# design.net
KiCad netlist of a schematic drawn in Altium Designer
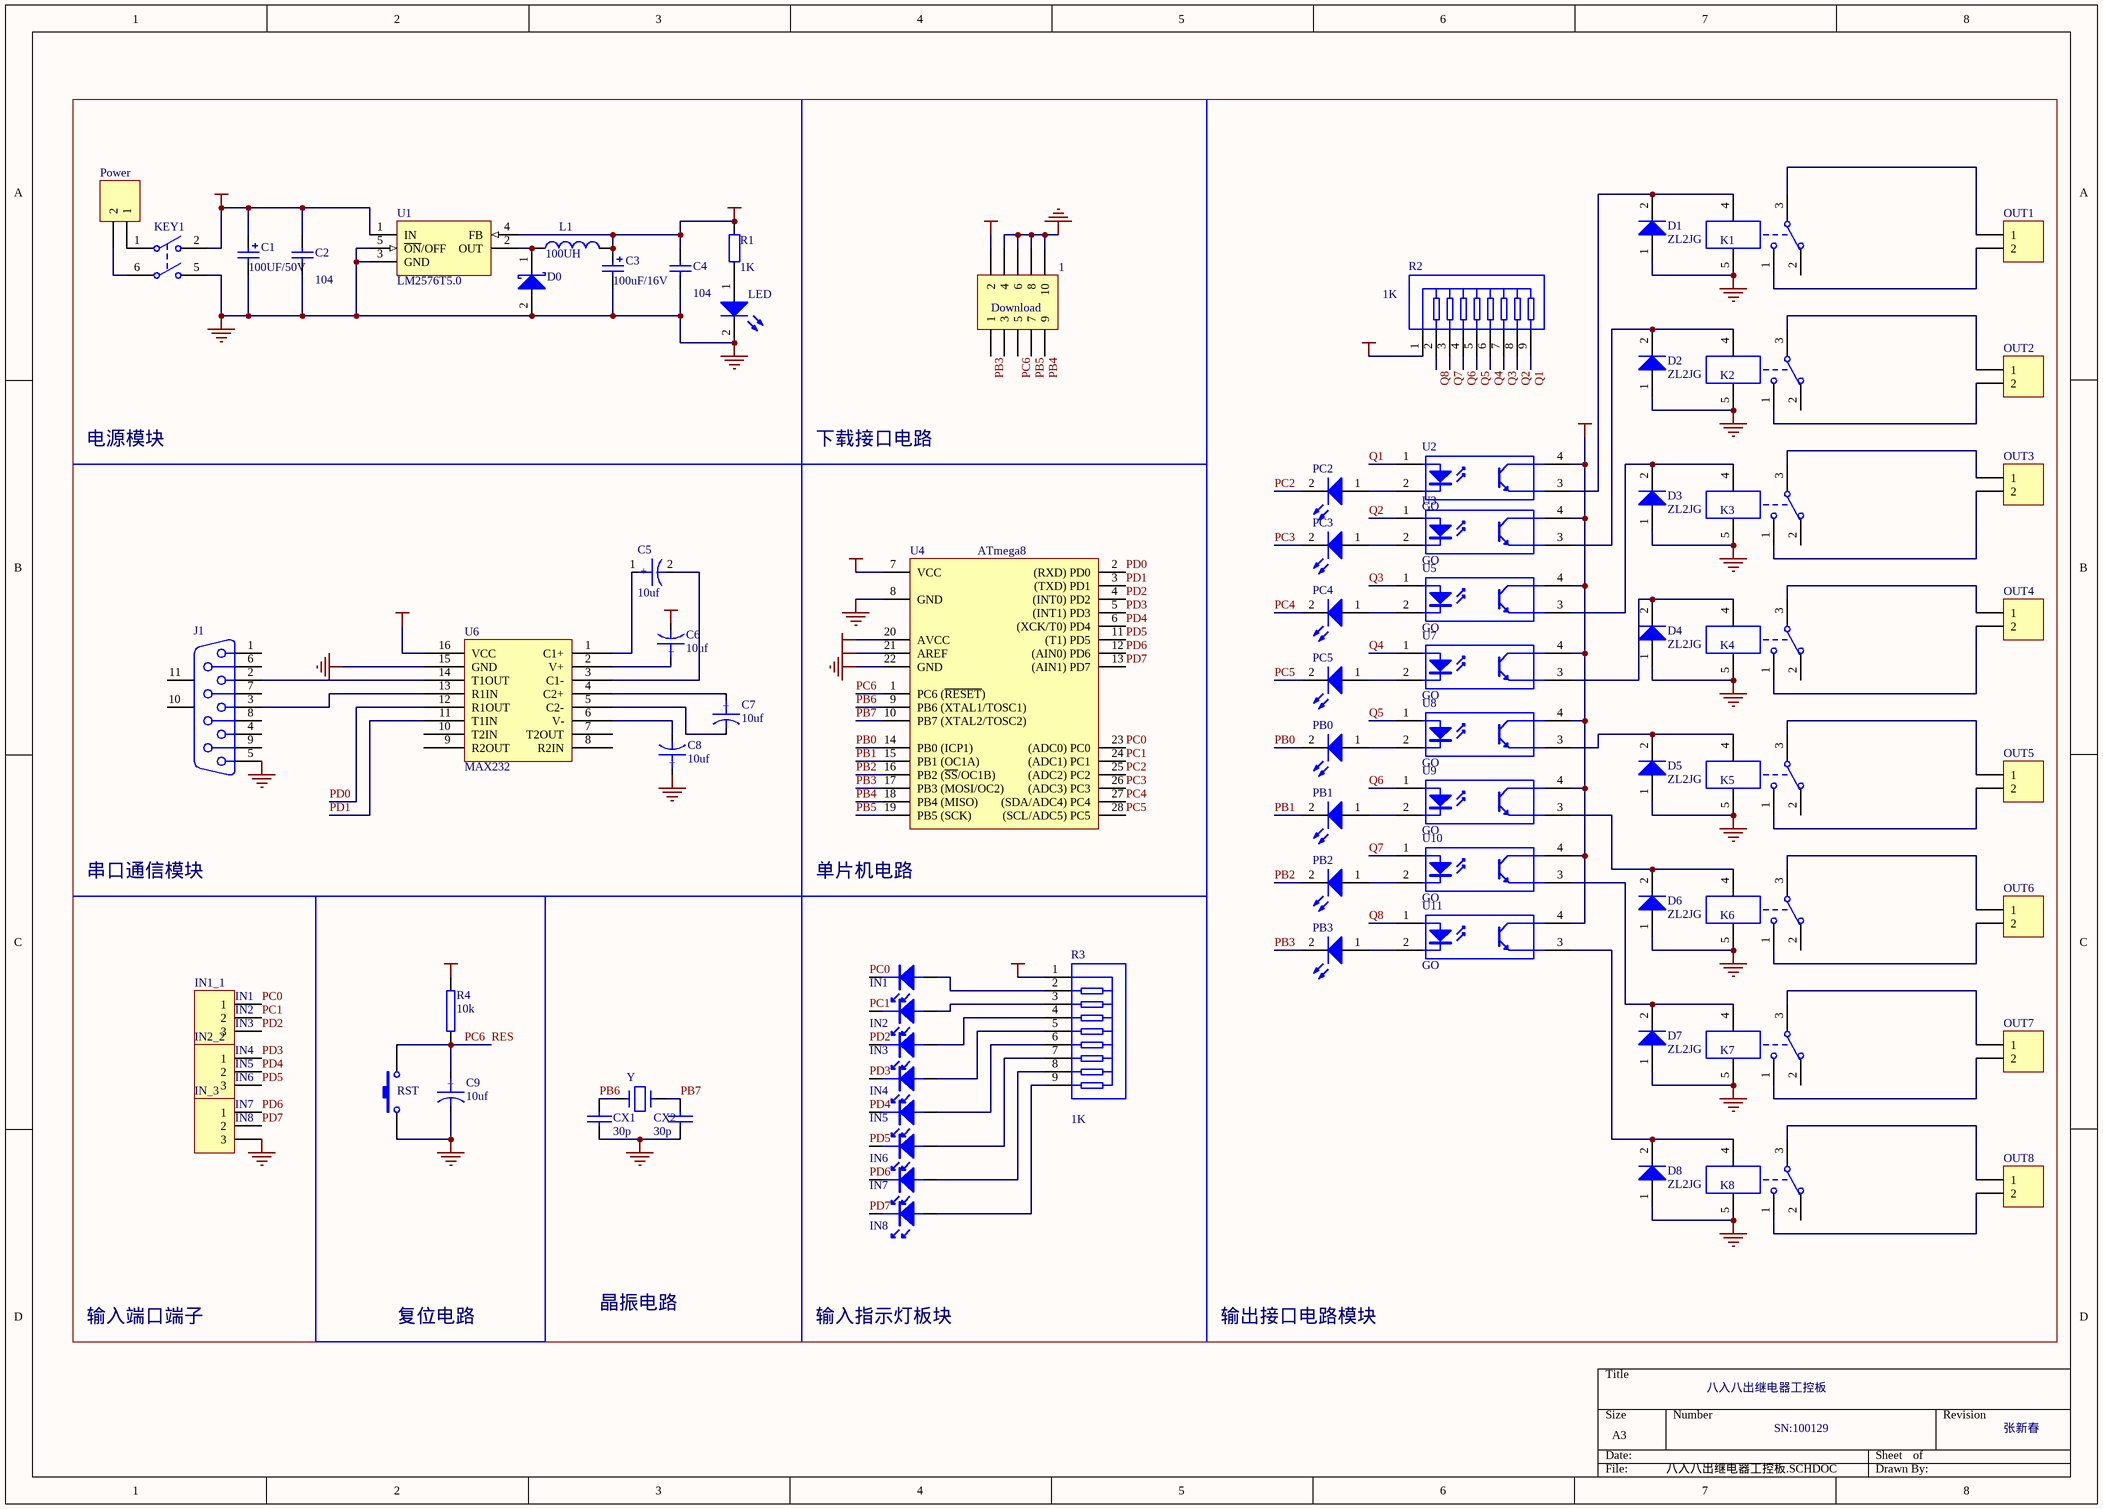
[diagram p0: 八入八出继电器工控板.SCHDOC]

(export (version "E")
  (design (tool "Eeschema 10.0.6"))
  (components
    (comp (ref "1")
      (value "Download")
      (footprint "HDR-2x5")
      (description "Header, 5-Pin, Dual row")
      (fields (field (name "PUBLISHER") "Altium Limited"))
      (libsource (lib "Miscellaneous Connectors") (part "Header 5X2"))
    )
    (comp (ref "C1")
      (value "100UF/50V")
      (footprint "C-DJ-6")
      (description "电解电容")
      (fields (field (name "Comment") "DJDR") (field (name "PUBLISHER") "Altium Limited"))
      (libsource (lib "zxcourhc") (part "DJDR"))
    )
    (comp (ref "C2")
      (value "104")
      (footprint "CPDR")
      (description "瓷片电容")
      (fields (field (name "Comment") "CPDR") (field (name "PUBLISHER") "Altium Limited"))
      (libsource (lib "zxcourhc") (part "CPDR"))
    )
    (comp (ref "C3")
      (value "100uF/16V")
      (footprint "C-DJ-6")
      (description "电解电容")
      (fields (field (name "Comment") "DJDR") (field (name "PUBLISHER") "Altium Limited"))
      (libsource (lib "zxcourhc") (part "DJDR"))
    )
    (comp (ref "C4")
      (value "104")
      (footprint "CPDR")
      (description "瓷片电容")
      (fields (field (name "Comment") "CPDR") (field (name "PUBLISHER") "Altium Limited"))
      (libsource (lib "zxcourhc") (part "CPDR"))
    )
    (comp (ref "C5")
      (value "10uf")
      (footprint "C-DJ-4")
      (description "Capacitor")
      (libsource (lib "") (part "CAPACITOR POL_1"))
    )
    (comp (ref "C6")
      (value "10uf")
      (footprint "C-DJ-4")
      (description "Capacitor")
      (libsource (lib "*") (part "CAPACITOR POL"))
    )
    (comp (ref "C7")
      (value "10uf")
      (footprint "C-DJ-4")
      (description "Capacitor")
      (libsource (lib "*") (part "CAPACITOR POL"))
    )
    (comp (ref "C8")
      (value "10uf")
      (footprint "C-DJ-4")
      (description "Capacitor")
      (libsource (lib "*") (part "CAPACITOR POL"))
    )
    (comp (ref "C9")
      (value "10uf")
      (footprint "C-DJ-4")
      (description "Capacitor")
      (libsource (lib "*") (part "CAPACITOR POL"))
    )
    (comp (ref "CX1")
      (value "30p")
      (footprint "HDR1X2")
      (description "Capacitor")
      (libsource (lib "*") (part "CAP"))
    )
    (comp (ref "CX2")
      (value "30p")
      (footprint "HDR1X2")
      (description "Capacitor")
      (libsource (lib "*") (part "CAP"))
    )
    (comp (ref "D0")
      (value "WY2JG")
      (footprint "ZCDZL")
      (description "稳压二级管")
      (fields (field (name "PUBLISHER") "Altium Limited"))
      (libsource (lib "zxcourhc") (part "WY2JG"))
    )
    (comp (ref "D1")
      (value "ZL2JG")
      (footprint "D-ZL-10")
      (description "整流二极管")
      (fields (field (name "PUBLISHER") "Altium Limited"))
      (libsource (lib "zxcourhc") (part "ZL2JG"))
    )
    (comp (ref "D2")
      (value "ZL2JG")
      (footprint "D-ZL-10")
      (description "整流二极管")
      (fields (field (name "PUBLISHER") "Altium Limited"))
      (libsource (lib "zxcourhc") (part "ZL2JG"))
    )
    (comp (ref "D3")
      (value "ZL2JG")
      (footprint "D-ZL-10")
      (description "整流二极管")
      (fields (field (name "PUBLISHER") "Altium Limited"))
      (libsource (lib "zxcourhc") (part "ZL2JG"))
    )
    (comp (ref "D4")
      (value "ZL2JG")
      (footprint "D-ZL-10")
      (description "整流二极管")
      (fields (field (name "PUBLISHER") "Altium Limited"))
      (libsource (lib "zxcourhc") (part "ZL2JG"))
    )
    (comp (ref "D5")
      (value "ZL2JG")
      (footprint "D-ZL-10")
      (description "整流二极管")
      (fields (field (name "PUBLISHER") "Altium Limited"))
      (libsource (lib "zxcourhc") (part "ZL2JG"))
    )
    (comp (ref "D6")
      (value "ZL2JG")
      (footprint "D-ZL-10")
      (description "整流二极管")
      (fields (field (name "PUBLISHER") "Altium Limited"))
      (libsource (lib "zxcourhc") (part "ZL2JG"))
    )
    (comp (ref "D7")
      (value "ZL2JG")
      (footprint "D-ZL-10")
      (description "整流二极管")
      (fields (field (name "PUBLISHER") "Altium Limited"))
      (libsource (lib "zxcourhc") (part "ZL2JG"))
    )
    (comp (ref "D8")
      (value "ZL2JG")
      (footprint "D-ZL-10")
      (description "整流二极管")
      (fields (field (name "PUBLISHER") "Altium Limited"))
      (libsource (lib "zxcourhc") (part "ZL2JG"))
    )
    (comp (ref "IN1") (value "LED") (footprint "HDR1X2") (libsource (lib "OldCow1 (1)") (part "LED")))
    (comp (ref "IN1_1")
      (value "PZ_3")
      (footprint "JK128_3")
      (description "排针——3")
      (fields (field (name "PUBLISHER") "Altium Limited"))
      (libsource (lib "zxcourhc") (part "PZ_3"))
    )
    (comp (ref "IN2") (value "LED") (footprint "HDR1X2") (libsource (lib "OldCow1 (1)") (part "LED")))
    (comp (ref "IN2_2")
      (value "PZ_3")
      (footprint "JK128_3")
      (description "排针——3")
      (fields (field (name "PUBLISHER") "Altium Limited"))
      (libsource (lib "zxcourhc") (part "PZ_3"))
    )
    (comp (ref "IN3") (value "LED") (footprint "HDR1X2") (libsource (lib "OldCow1 (1)") (part "LED")))
    (comp (ref "IN4") (value "LED") (footprint "HDR1X2") (libsource (lib "OldCow1 (1)") (part "LED")))
    (comp (ref "IN5") (value "LED") (footprint "HDR1X2") (libsource (lib "OldCow1 (1)") (part "LED")))
    (comp (ref "IN6") (value "LED") (footprint "HDR1X2") (libsource (lib "OldCow1 (1)") (part "LED")))
    (comp (ref "IN7") (value "LED") (footprint "HDR1X2") (libsource (lib "OldCow1 (1)") (part "LED")))
    (comp (ref "IN8") (value "LED") (footprint "HDR1X2") (libsource (lib "OldCow1 (1)") (part "LED")))
    (comp (ref "IN_3")
      (value "~")
      (footprint "JK128_3")
      (description "排针——3")
      (fields (field (name "PUBLISHER") "Altium Limited"))
      (libsource (lib "zxcourhc") (part "PZ_3"))
    )
    (comp (ref "J1")
      (value "D Connector 9")
      (footprint "DSUB1.385-2H9")
      (description "Receptacle Assembly, 9 Position, Right Angle")
      (fields (field (name "PUBLISHER") "Altium Limited"))
      (libsource (lib "Miscellaneous Connectors") (part "D Connector 9"))
    )
    (comp (ref "K1")
      (value "JDQYCK")
      (footprint "JQC-3F/T73")
      (description "继电器——1常开1常闭")
      (fields (field (name "PUBLISHER") "Altium Limited"))
      (libsource (lib "zxcourhc") (part "JDQYCK"))
    )
    (comp (ref "K2")
      (value "JDQYCK")
      (footprint "JQC-3F/T73")
      (description "继电器——1常开1常闭")
      (fields (field (name "PUBLISHER") "Altium Limited"))
      (libsource (lib "zxcourhc") (part "JDQYCK"))
    )
    (comp (ref "K3")
      (value "JDQYCK")
      (footprint "JQC-3F/T73")
      (description "继电器——1常开1常闭")
      (fields (field (name "PUBLISHER") "Altium Limited"))
      (libsource (lib "zxcourhc") (part "JDQYCK"))
    )
    (comp (ref "K4")
      (value "JDQYCK")
      (footprint "JQC-3F/T73")
      (description "继电器——1常开1常闭")
      (fields (field (name "PUBLISHER") "Altium Limited"))
      (libsource (lib "zxcourhc") (part "JDQYCK"))
    )
    (comp (ref "K5")
      (value "JDQYCK")
      (footprint "JQC-3F/T73")
      (description "继电器——1常开1常闭")
      (fields (field (name "PUBLISHER") "Altium Limited"))
      (libsource (lib "zxcourhc") (part "JDQYCK"))
    )
    (comp (ref "K6")
      (value "JDQYCK")
      (footprint "JQC-3F/T73")
      (description "继电器——1常开1常闭")
      (fields (field (name "PUBLISHER") "Altium Limited"))
      (libsource (lib "zxcourhc") (part "JDQYCK"))
    )
    (comp (ref "K7")
      (value "JDQYCK")
      (footprint "JQC-3F/T73")
      (description "继电器——1常开1常闭")
      (fields (field (name "PUBLISHER") "Altium Limited"))
      (libsource (lib "zxcourhc") (part "JDQYCK"))
    )
    (comp (ref "K8")
      (value "JDQYCK")
      (footprint "JQC-3F/T73")
      (description "继电器——1常开1常闭")
      (fields (field (name "PUBLISHER") "Altium Limited"))
      (libsource (lib "zxcourhc") (part "JDQYCK"))
    )
    (comp (ref "KEY1")
      (value "SW-DPST")
      (footprint "DPDT-6")
      (description "Double-Pole, Single-Throw Switch")
      (fields (field (name "PUBLISHER") "Altium Limited"))
      (libsource (lib "Miscellaneous Devices") (part "SW-DPST"))
    )
    (comp (ref "L1")
      (value "100UH")
      (footprint "L_DG")
      (description "电感")
      (fields (field (name "Comment") "DG") (field (name "PUBLISHER") "Altium Limited"))
      (libsource (lib "zxcourhc") (part "DG"))
    )
    (comp (ref "LED")
      (value "LED")
      (footprint "LED_D")
      (description "发光二极管")
      (fields (field (name "PUBLISHER") "Altium Limited"))
      (libsource (lib "zxcourhc") (part "LED"))
    )
    (comp (ref "OUT1")
      (value "PZ_2")
      (footprint "DYDZ")
      (description "排针——2")
      (fields (field (name "PUBLISHER") "Altium Limited"))
      (libsource (lib "zxcourhc") (part "PZ_2"))
    )
    (comp (ref "OUT2")
      (value "PZ_2")
      (footprint "DYDZ")
      (description "排针——2")
      (fields (field (name "PUBLISHER") "Altium Limited"))
      (libsource (lib "zxcourhc") (part "PZ_2"))
    )
    (comp (ref "OUT3")
      (value "PZ_2")
      (footprint "DYDZ")
      (description "排针——2")
      (fields (field (name "PUBLISHER") "Altium Limited"))
      (libsource (lib "zxcourhc") (part "PZ_2"))
    )
    (comp (ref "OUT4")
      (value "PZ_2")
      (footprint "DYDZ")
      (description "排针——2")
      (fields (field (name "PUBLISHER") "Altium Limited"))
      (libsource (lib "zxcourhc") (part "PZ_2"))
    )
    (comp (ref "OUT5")
      (value "PZ_2")
      (footprint "DYDZ")
      (description "排针——2")
      (fields (field (name "PUBLISHER") "Altium Limited"))
      (libsource (lib "zxcourhc") (part "PZ_2"))
    )
    (comp (ref "OUT6")
      (value "PZ_2")
      (footprint "DYDZ")
      (description "排针——2")
      (fields (field (name "PUBLISHER") "Altium Limited"))
      (libsource (lib "zxcourhc") (part "PZ_2"))
    )
    (comp (ref "OUT7")
      (value "PZ_2")
      (footprint "DYDZ")
      (description "排针——2")
      (fields (field (name "PUBLISHER") "Altium Limited"))
      (libsource (lib "zxcourhc") (part "PZ_2"))
    )
    (comp (ref "OUT8")
      (value "PZ_2")
      (footprint "DYDZ")
      (description "排针——2")
      (fields (field (name "PUBLISHER") "Altium Limited"))
      (libsource (lib "zxcourhc") (part "PZ_2"))
    )
    (comp (ref "PB0")
      (value "~")
      (footprint "CPDR")
      (description "发光二极管")
      (fields (field (name "PUBLISHER") "Altium Limited"))
      (libsource (lib "zxcourhc") (part "LED"))
    )
    (comp (ref "PB1")
      (value "~")
      (footprint "CPDR")
      (description "发光二极管")
      (fields (field (name "PUBLISHER") "Altium Limited"))
      (libsource (lib "zxcourhc") (part "LED"))
    )
    (comp (ref "PB2")
      (value "~")
      (footprint "CPDR")
      (description "发光二极管")
      (fields (field (name "PUBLISHER") "Altium Limited"))
      (libsource (lib "zxcourhc") (part "LED"))
    )
    (comp (ref "PB3")
      (value "~")
      (footprint "CPDR")
      (description "发光二极管")
      (fields (field (name "PUBLISHER") "Altium Limited"))
      (libsource (lib "zxcourhc") (part "LED"))
    )
    (comp (ref "PC2")
      (value "~")
      (footprint "CPDR")
      (description "发光二极管")
      (fields (field (name "PUBLISHER") "Altium Limited"))
      (libsource (lib "zxcourhc") (part "LED"))
    )
    (comp (ref "PC3")
      (value "~")
      (footprint "CPDR")
      (description "发光二极管")
      (fields (field (name "PUBLISHER") "Altium Limited"))
      (libsource (lib "zxcourhc") (part "LED"))
    )
    (comp (ref "PC4")
      (value "~")
      (footprint "CPDR")
      (description "发光二极管")
      (fields (field (name "PUBLISHER") "Altium Limited"))
      (libsource (lib "zxcourhc") (part "LED"))
    )
    (comp (ref "PC5")
      (value "~")
      (footprint "CPDR")
      (description "发光二极管")
      (fields (field (name "PUBLISHER") "Altium Limited"))
      (libsource (lib "zxcourhc") (part "LED"))
    )
    (comp (ref "Power")
      (value "PZ_2")
      (footprint "JK128_2")
      (description "排针——2")
      (fields (field (name "PUBLISHER") "Altium Limited"))
      (libsource (lib "") (part "PZ_2_1"))
    )
    (comp (ref "R1")
      (value "1K")
      (footprint "RSE")
      (description "电阻")
      (fields (field (name "Comment") "Res") (field (name "PUBLISHER") "Altium Limited"))
      (libsource (lib "zxcourhc") (part "Res"))
    )
    (comp (ref "R2")
      (value "1K")
      (footprint "HDR-9")
      (description "8位排阻")
      (fields (field (name "PUBLISHER") "Altium Limited"))
      (libsource (lib "zxcourhc") (part "Res PZ_8"))
    )
    (comp (ref "R3")
      (value "1K")
      (footprint "HDR-9")
      (description "8位排阻")
      (fields (field (name "PUBLISHER") "Altium Limited"))
      (libsource (lib "zxcourhc") (part "Res PZ_8"))
    )
    (comp (ref "R4") (value "10k") (footprint "RSE") (libsource (lib "*") (part "RES2")))
    (comp (ref "RST")
      (value "~")
      (footprint "an-6*6")
      (description "Switch")
      (fields (field (name "PUBLISHER") "Altium Limited"))
      (libsource (lib "Miscellaneous Devices") (part "SW-PB"))
    )
    (comp (ref "U1")
      (value "LM2576T5.0")
      (footprint "T05A")
      (description "Simple Switcher 3A Step Down Voltage Regulator")
      (fields (field (name "PUBLISHER") "Altium Limited"))
      (libsource (lib "NSC Power Mgt Switching Regulator") (part "LM2576HVT-3.3"))
    )
    (comp (ref "U2")
      (value "GO")
      (footprint "DIP-4")
      (description "光耦")
      (fields (field (name "PUBLISHER") "Altium Limited"))
      (libsource (lib "zxcourhc") (part "GO"))
    )
    (comp (ref "U3")
      (value "GO")
      (footprint "DIP-4")
      (description "光耦")
      (fields (field (name "PUBLISHER") "Altium Limited"))
      (libsource (lib "zxcourhc") (part "GO"))
    )
    (comp (ref "U4")
      (value "ATmega8")
      (footprint "DIP-28")
      (description "8 位微处理器/28引脚")
      (fields (field (name "发布者") "磊元工作室"))
      (libsource (lib "MCU") (part "ATmega8-P"))
    )
    (comp (ref "U5")
      (value "GO")
      (footprint "DIP-4")
      (description "光耦")
      (fields (field (name "PUBLISHER") "Altium Limited"))
      (libsource (lib "zxcourhc") (part "GO"))
    )
    (comp (ref "U6") (value "MAX232") (footprint "DIP16") (libsource (lib "*") (part "MAX232")))
    (comp (ref "U7")
      (value "GO")
      (footprint "DIP-4")
      (description "光耦")
      (fields (field (name "PUBLISHER") "Altium Limited"))
      (libsource (lib "zxcourhc") (part "GO"))
    )
    (comp (ref "U8")
      (value "GO")
      (footprint "DIP-4")
      (description "光耦")
      (fields (field (name "PUBLISHER") "Altium Limited"))
      (libsource (lib "zxcourhc") (part "GO"))
    )
    (comp (ref "U9")
      (value "GO")
      (footprint "DIP-4")
      (description "光耦")
      (fields (field (name "PUBLISHER") "Altium Limited"))
      (libsource (lib "zxcourhc") (part "GO"))
    )
    (comp (ref "U10")
      (value "GO")
      (footprint "DIP-4")
      (description "光耦")
      (fields (field (name "PUBLISHER") "Altium Limited"))
      (libsource (lib "zxcourhc") (part "GO"))
    )
    (comp (ref "U11")
      (value "GO")
      (footprint "DIP-4")
      (description "光耦")
      (fields (field (name "PUBLISHER") "Altium Limited"))
      (libsource (lib "zxcourhc") (part "GO"))
    )
    (comp (ref "Y1")
      (value "Y")
      (footprint "JZ_ZC")
      (description "Crystal")
      (libsource (lib "*") (part "CRYSTAL"))
    )
  )
  (nets
    (net (code "1") (name "+12V") (class "Default")
      (node (ref "C1") (pin "1") (pinfunction "1_1") (pintype "passive"))
      (node (ref "C2") (pin "2") (pinfunction "2_2") (pintype "passive"))
      (node (ref "KEY1") (pin "2") (pinfunction "NO1_2") (pintype "passive"))
      (node (ref "U1") (pin "1") (pinfunction "IN_1") (pintype "power_in"))
      (node (ref "U10") (pin "4") (pinfunction "C_4") (pintype "passive"))
      (node (ref "U11") (pin "4") (pinfunction "C_4") (pintype "passive"))
      (node (ref "U2") (pin "4") (pinfunction "C_4") (pintype "passive"))
      (node (ref "U3") (pin "4") (pinfunction "C_4") (pintype "passive"))
      (node (ref "U5") (pin "4") (pinfunction "C_4") (pintype "passive"))
      (node (ref "U7") (pin "4") (pinfunction "C_4") (pintype "passive"))
      (node (ref "U8") (pin "4") (pinfunction "C_4") (pintype "passive"))
      (node (ref "U9") (pin "4") (pinfunction "C_4") (pintype "passive"))
    )
    (net (code "2") (name "/PB0") (class "Default")
      (node (ref "PB0") (pin "2") (pinfunction "K_2") (pintype "passive"))
      (node (ref "U4") (pin "14") (pinfunction "PB0_(ICP1)_14") (pintype "passive"))
    )
    (net (code "3") (name "/PB1") (class "Default")
      (node (ref "PB1") (pin "2") (pinfunction "K_2") (pintype "passive"))
      (node (ref "U4") (pin "15") (pinfunction "PB1_(OC1A)_15") (pintype "passive"))
    )
    (net (code "4") (name "/PB2") (class "Default")
      (node (ref "PB2") (pin "2") (pinfunction "K_2") (pintype "passive"))
      (node (ref "U4") (pin "16") (pinfunction "PB2_(~{SS}/OC1B)_16") (pintype "passive"))
    )
    (net (code "5") (name "/PB3") (class "Default")
      (node (ref "1") (pin "1") (pinfunction "1_1") (pintype "passive"))
      (node (ref "PB3") (pin "2") (pinfunction "K_2") (pintype "passive"))
      (node (ref "U4") (pin "17") (pinfunction "PB3_(MOSI/OC2)_17") (pintype "passive"))
    )
    (net (code "6") (name "/PB4") (class "Default")
      (node (ref "1") (pin "9") (pinfunction "9_9") (pintype "passive"))
      (node (ref "U4") (pin "18") (pinfunction "PB4_(MISO)_18") (pintype "passive"))
    )
    (net (code "7") (name "/PB5") (class "Default")
      (node (ref "1") (pin "7") (pinfunction "7_7") (pintype "passive"))
      (node (ref "U4") (pin "19") (pinfunction "PB5_(SCK)_19") (pintype "passive"))
    )
    (net (code "8") (name "/PB6") (class "Default")
      (node (ref "CX1") (pin "1") (pinfunction "1_1") (pintype "passive"))
      (node (ref "U4") (pin "9") (pinfunction "PB6_(XTAL1/TOSC1)_9") (pintype "passive"))
      (node (ref "Y1") (pin "2") (pinfunction "2_2") (pintype "passive"))
    )
    (net (code "9") (name "/PB7") (class "Default")
      (node (ref "CX2") (pin "1") (pinfunction "1_1") (pintype "passive"))
      (node (ref "U4") (pin "10") (pinfunction "PB7_(XTAL2/TOSC2)_10") (pintype "passive"))
      (node (ref "Y1") (pin "1") (pinfunction "1_1") (pintype "passive"))
    )
    (net (code "10") (name "/PC0") (class "Default")
      (node (ref "IN1") (pin "2") (pinfunction "K_2") (pintype "passive"))
      (node (ref "IN1_1") (pin "1") (pinfunction "1_1") (pintype "passive"))
      (node (ref "U4") (pin "23") (pinfunction "(ADC0)_PC0_23") (pintype "passive"))
    )
    (net (code "11") (name "/PC1") (class "Default")
      (node (ref "IN1_1") (pin "2") (pinfunction "2_2") (pintype "passive"))
      (node (ref "IN2") (pin "2") (pinfunction "K_2") (pintype "passive"))
      (node (ref "U4") (pin "24") (pinfunction "(ADC1)_PC1_24") (pintype "passive"))
    )
    (net (code "12") (name "/PC2") (class "Default")
      (node (ref "PC2") (pin "2") (pinfunction "K_2") (pintype "passive"))
      (node (ref "U4") (pin "25") (pinfunction "(ADC2)_PC2_25") (pintype "passive"))
    )
    (net (code "13") (name "/PC3") (class "Default")
      (node (ref "PC3") (pin "2") (pinfunction "K_2") (pintype "passive"))
      (node (ref "U4") (pin "26") (pinfunction "(ADC3)_PC3_26") (pintype "passive"))
    )
    (net (code "14") (name "/PC4") (class "Default")
      (node (ref "PC4") (pin "2") (pinfunction "K_2") (pintype "passive"))
      (node (ref "U4") (pin "27") (pinfunction "(SDA/ADC4)_PC4_27") (pintype "passive"))
    )
    (net (code "15") (name "/PC5") (class "Default")
      (node (ref "PC5") (pin "2") (pinfunction "K_2") (pintype "passive"))
      (node (ref "U4") (pin "28") (pinfunction "(SCL/ADC5)_PC5_28") (pintype "passive"))
    )
    (net (code "16") (name "/PC6") (class "Default")
      (node (ref "1") (pin "5") (pinfunction "5_5") (pintype "passive"))
      (node (ref "C9") (pin "1") (pinfunction "1_1") (pintype "passive"))
      (node (ref "R4") (pin "1") (pinfunction "1_1") (pintype "passive"))
      (node (ref "RST") (pin "1") (pinfunction "1_1") (pintype "passive"))
      (node (ref "U4") (pin "1") (pinfunction "PC6_(~{RESET})_1") (pintype "passive"))
    )
    (net (code "17") (name "/PD0") (class "Default")
      (node (ref "U4") (pin "2") (pinfunction "(RXD)_PD0_2") (pintype "passive"))
      (node (ref "U6") (pin "12") (pinfunction "R1OUT_12") (pintype "passive"))
    )
    (net (code "18") (name "/PD1") (class "Default")
      (node (ref "U4") (pin "3") (pinfunction "(TXD)_PD1_3") (pintype "passive"))
      (node (ref "U6") (pin "11") (pinfunction "T1IN_11") (pintype "passive"))
    )
    (net (code "19") (name "/PD2") (class "Default")
      (node (ref "IN1_1") (pin "3") (pinfunction "3_3") (pintype "passive"))
      (node (ref "IN3") (pin "2") (pinfunction "K_2") (pintype "passive"))
      (node (ref "U4") (pin "4") (pinfunction "(INT0)_PD2_4") (pintype "passive"))
    )
    (net (code "20") (name "/PD3") (class "Default")
      (node (ref "IN2_2") (pin "1") (pinfunction "1_1") (pintype "passive"))
      (node (ref "IN4") (pin "2") (pinfunction "K_2") (pintype "passive"))
      (node (ref "U4") (pin "5") (pinfunction "(INT1)_PD3_5") (pintype "passive"))
    )
    (net (code "21") (name "/PD4") (class "Default")
      (node (ref "IN2_2") (pin "2") (pinfunction "2_2") (pintype "passive"))
      (node (ref "IN5") (pin "2") (pinfunction "K_2") (pintype "passive"))
      (node (ref "U4") (pin "6") (pinfunction "(XCK/T0)_PD4_6") (pintype "passive"))
    )
    (net (code "22") (name "/PD5") (class "Default")
      (node (ref "IN2_2") (pin "3") (pinfunction "3_3") (pintype "passive"))
      (node (ref "IN6") (pin "2") (pinfunction "K_2") (pintype "passive"))
      (node (ref "U4") (pin "11") (pinfunction "(T1)_PD5_11") (pintype "passive"))
    )
    (net (code "23") (name "/PD6") (class "Default")
      (node (ref "IN7") (pin "2") (pinfunction "K_2") (pintype "passive"))
      (node (ref "IN_3") (pin "1") (pinfunction "1_1") (pintype "passive"))
      (node (ref "U4") (pin "12") (pinfunction "(AIN0)_PD6_12") (pintype "passive"))
    )
    (net (code "24") (name "/PD7") (class "Default")
      (node (ref "IN8") (pin "2") (pinfunction "K_2") (pintype "passive"))
      (node (ref "IN_3") (pin "2") (pinfunction "2_2") (pintype "passive"))
      (node (ref "U4") (pin "13") (pinfunction "(AIN1)_PD7_13") (pintype "passive"))
    )
    (net (code "25") (name "/Q1") (class "Default")
      (node (ref "R2") (pin "9") (pinfunction "9_9") (pintype "passive"))
      (node (ref "U2") (pin "1") (pinfunction "A_1") (pintype "passive"))
    )
    (net (code "26") (name "/Q2") (class "Default")
      (node (ref "R2") (pin "8") (pinfunction "8_8") (pintype "passive"))
      (node (ref "U3") (pin "1") (pinfunction "A_1") (pintype "passive"))
    )
    (net (code "27") (name "/Q3") (class "Default")
      (node (ref "R2") (pin "7") (pinfunction "7_7") (pintype "passive"))
      (node (ref "U5") (pin "1") (pinfunction "A_1") (pintype "passive"))
    )
    (net (code "28") (name "/Q4") (class "Default")
      (node (ref "R2") (pin "6") (pinfunction "6_6") (pintype "passive"))
      (node (ref "U7") (pin "1") (pinfunction "A_1") (pintype "passive"))
    )
    (net (code "29") (name "/Q5") (class "Default")
      (node (ref "R2") (pin "5") (pinfunction "5_5") (pintype "passive"))
      (node (ref "U8") (pin "1") (pinfunction "A_1") (pintype "passive"))
    )
    (net (code "30") (name "/Q6") (class "Default")
      (node (ref "R2") (pin "4") (pinfunction "4_4") (pintype "passive"))
      (node (ref "U9") (pin "1") (pinfunction "A_1") (pintype "passive"))
    )
    (net (code "31") (name "/Q7") (class "Default")
      (node (ref "R2") (pin "3") (pinfunction "3_3") (pintype "passive"))
      (node (ref "U10") (pin "1") (pinfunction "A_1") (pintype "passive"))
    )
    (net (code "32") (name "/Q8") (class "Default")
      (node (ref "R2") (pin "2") (pinfunction "2_2") (pintype "passive"))
      (node (ref "U11") (pin "1") (pinfunction "A_1") (pintype "passive"))
    )
    (net (code "33") (name "GND") (class "Default")
      (node (ref "1") (pin "10") (pinfunction "10_10") (pintype "passive"))
      (node (ref "1") (pin "4") (pinfunction "4_4") (pintype "passive"))
      (node (ref "1") (pin "6") (pinfunction "6_6") (pintype "passive"))
      (node (ref "1") (pin "8") (pinfunction "8_8") (pintype "passive"))
      (node (ref "C1") (pin "2") (pinfunction "2_2") (pintype "passive"))
      (node (ref "C2") (pin "1") (pinfunction "1_1") (pintype "passive"))
      (node (ref "C3") (pin "2") (pinfunction "2_2") (pintype "passive"))
      (node (ref "C4") (pin "1") (pinfunction "1_1") (pintype "passive"))
      (node (ref "C8") (pin "1") (pinfunction "1_1") (pintype "passive"))
      (node (ref "C9") (pin "2") (pinfunction "2_2") (pintype "passive"))
      (node (ref "CX1") (pin "2") (pinfunction "2_2") (pintype "passive"))
      (node (ref "CX2") (pin "2") (pinfunction "2_2") (pintype "passive"))
      (node (ref "D0") (pin "2") (pinfunction "K_2") (pintype "passive"))
      (node (ref "D1") (pin "1") (pinfunction "A_1") (pintype "passive"))
      (node (ref "D2") (pin "1") (pinfunction "A_1") (pintype "passive"))
      (node (ref "D3") (pin "1") (pinfunction "A_1") (pintype "passive"))
      (node (ref "D4") (pin "1") (pinfunction "A_1") (pintype "passive"))
      (node (ref "D5") (pin "1") (pinfunction "A_1") (pintype "passive"))
      (node (ref "D6") (pin "1") (pinfunction "A_1") (pintype "passive"))
      (node (ref "D7") (pin "1") (pinfunction "A_1") (pintype "passive"))
      (node (ref "D8") (pin "1") (pinfunction "A_1") (pintype "passive"))
      (node (ref "IN_3") (pin "3") (pinfunction "3_3") (pintype "passive"))
      (node (ref "J1") (pin "5") (pinfunction "5_5") (pintype "passive"))
      (node (ref "K1") (pin "5") (pinfunction "5_5") (pintype "passive"))
      (node (ref "K2") (pin "5") (pinfunction "5_5") (pintype "passive"))
      (node (ref "K3") (pin "5") (pinfunction "5_5") (pintype "passive"))
      (node (ref "K4") (pin "5") (pinfunction "5_5") (pintype "passive"))
      (node (ref "K5") (pin "5") (pinfunction "5_5") (pintype "passive"))
      (node (ref "K6") (pin "5") (pinfunction "5_5") (pintype "passive"))
      (node (ref "K7") (pin "5") (pinfunction "5_5") (pintype "passive"))
      (node (ref "K8") (pin "5") (pinfunction "5_5") (pintype "passive"))
      (node (ref "KEY1") (pin "5") (pinfunction "NO2_5") (pintype "passive"))
      (node (ref "LED") (pin "2") (pinfunction "K_2") (pintype "passive"))
      (node (ref "RST") (pin "2") (pinfunction "2_2") (pintype "passive"))
      (node (ref "U1") (pin "3") (pinfunction "GND_3") (pintype "power_in"))
      (node (ref "U1") (pin "5") (pinfunction "~{ON}/OFF_5") (pintype "input"))
      (node (ref "U4") (pin "22") (pinfunction "GND_22") (pintype "passive"))
      (node (ref "U4") (pin "8") (pinfunction "GND_8") (pintype "passive"))
      (node (ref "U6") (pin "15") (pinfunction "GND_15") (pintype "passive"))
    )
    (net (code "34") (name "Net-(D0-A)") (class "Default")
      (node (ref "D0") (pin "1") (pinfunction "A_1") (pintype "passive"))
      (node (ref "L1") (pin "1") (pinfunction "1_1") (pintype "passive"))
      (node (ref "U1") (pin "2") (pinfunction "OUT_2") (pintype "power_in"))
    )
    (net (code "35") (name "Net-(D1-K)") (class "Default")
      (node (ref "D1") (pin "2") (pinfunction "K_2") (pintype "passive"))
      (node (ref "K1") (pin "4") (pinfunction "4_4") (pintype "passive"))
      (node (ref "U2") (pin "3") (pinfunction "E_3") (pintype "passive"))
    )
    (net (code "36") (name "Net-(D2-K)") (class "Default")
      (node (ref "D2") (pin "2") (pinfunction "K_2") (pintype "passive"))
      (node (ref "K2") (pin "4") (pinfunction "4_4") (pintype "passive"))
      (node (ref "U3") (pin "3") (pinfunction "E_3") (pintype "passive"))
    )
    (net (code "37") (name "Net-(D3-K)") (class "Default")
      (node (ref "D3") (pin "2") (pinfunction "K_2") (pintype "passive"))
      (node (ref "K3") (pin "4") (pinfunction "4_4") (pintype "passive"))
      (node (ref "U5") (pin "3") (pinfunction "E_3") (pintype "passive"))
    )
    (net (code "38") (name "Net-(D4-K)") (class "Default")
      (node (ref "D4") (pin "2") (pinfunction "K_2") (pintype "passive"))
      (node (ref "K4") (pin "4") (pinfunction "4_4") (pintype "passive"))
      (node (ref "U7") (pin "3") (pinfunction "E_3") (pintype "passive"))
    )
    (net (code "39") (name "Net-(D5-K)") (class "Default")
      (node (ref "D5") (pin "2") (pinfunction "K_2") (pintype "passive"))
      (node (ref "K5") (pin "4") (pinfunction "4_4") (pintype "passive"))
      (node (ref "U8") (pin "3") (pinfunction "E_3") (pintype "passive"))
    )
    (net (code "40") (name "Net-(D6-K)") (class "Default")
      (node (ref "D6") (pin "2") (pinfunction "K_2") (pintype "passive"))
      (node (ref "K6") (pin "4") (pinfunction "4_4") (pintype "passive"))
      (node (ref "U9") (pin "3") (pinfunction "E_3") (pintype "passive"))
    )
    (net (code "41") (name "Net-(D7-K)") (class "Default")
      (node (ref "D7") (pin "2") (pinfunction "K_2") (pintype "passive"))
      (node (ref "K7") (pin "4") (pinfunction "4_4") (pintype "passive"))
      (node (ref "U10") (pin "3") (pinfunction "E_3") (pintype "passive"))
    )
    (net (code "42") (name "Net-(D8-K)") (class "Default")
      (node (ref "D8") (pin "2") (pinfunction "K_2") (pintype "passive"))
      (node (ref "K8") (pin "4") (pinfunction "4_4") (pintype "passive"))
      (node (ref "U11") (pin "3") (pinfunction "E_3") (pintype "passive"))
    )
    (net (code "43") (name "Net-(IN1-A)") (class "Default")
      (node (ref "IN1") (pin "1") (pinfunction "A_1") (pintype "passive"))
      (node (ref "R3") (pin "2") (pinfunction "2_2") (pintype "passive"))
    )
    (net (code "44") (name "Net-(IN2-A)") (class "Default")
      (node (ref "IN2") (pin "1") (pinfunction "A_1") (pintype "passive"))
      (node (ref "R3") (pin "3") (pinfunction "3_3") (pintype "passive"))
    )
    (net (code "45") (name "Net-(IN3-A)") (class "Default")
      (node (ref "IN3") (pin "1") (pinfunction "A_1") (pintype "passive"))
      (node (ref "R3") (pin "4") (pinfunction "4_4") (pintype "passive"))
    )
    (net (code "46") (name "Net-(IN4-A)") (class "Default")
      (node (ref "IN4") (pin "1") (pinfunction "A_1") (pintype "passive"))
      (node (ref "R3") (pin "5") (pinfunction "5_5") (pintype "passive"))
    )
    (net (code "47") (name "Net-(IN5-A)") (class "Default")
      (node (ref "IN5") (pin "1") (pinfunction "A_1") (pintype "passive"))
      (node (ref "R3") (pin "6") (pinfunction "6_6") (pintype "passive"))
    )
    (net (code "48") (name "Net-(IN6-A)") (class "Default")
      (node (ref "IN6") (pin "1") (pinfunction "A_1") (pintype "passive"))
      (node (ref "R3") (pin "7") (pinfunction "7_7") (pintype "passive"))
    )
    (net (code "49") (name "Net-(IN7-A)") (class "Default")
      (node (ref "IN7") (pin "1") (pinfunction "A_1") (pintype "passive"))
      (node (ref "R3") (pin "8") (pinfunction "8_8") (pintype "passive"))
    )
    (net (code "50") (name "Net-(IN8-A)") (class "Default")
      (node (ref "IN8") (pin "1") (pinfunction "A_1") (pintype "passive"))
      (node (ref "R3") (pin "9") (pinfunction "9_9") (pintype "passive"))
    )
    (net (code "51") (name "Net-(K1-Pad1)") (class "Default")
      (node (ref "K1") (pin "1") (pinfunction "1_1") (pintype "passive"))
      (node (ref "OUT1") (pin "2") (pinfunction "2_2") (pintype "passive"))
    )
    (net (code "52") (name "Net-(K1-Pad3)") (class "Default")
      (node (ref "K1") (pin "3") (pinfunction "3_3") (pintype "passive"))
      (node (ref "OUT1") (pin "1") (pinfunction "1_1") (pintype "passive"))
    )
    (net (code "53") (name "Net-(K2-Pad1)") (class "Default")
      (node (ref "K2") (pin "1") (pinfunction "1_1") (pintype "passive"))
      (node (ref "OUT2") (pin "2") (pinfunction "2_2") (pintype "passive"))
    )
    (net (code "54") (name "Net-(K2-Pad3)") (class "Default")
      (node (ref "K2") (pin "3") (pinfunction "3_3") (pintype "passive"))
      (node (ref "OUT2") (pin "1") (pinfunction "1_1") (pintype "passive"))
    )
    (net (code "55") (name "Net-(K3-Pad1)") (class "Default")
      (node (ref "K3") (pin "1") (pinfunction "1_1") (pintype "passive"))
      (node (ref "OUT3") (pin "2") (pinfunction "2_2") (pintype "passive"))
    )
    (net (code "56") (name "Net-(K3-Pad3)") (class "Default")
      (node (ref "K3") (pin "3") (pinfunction "3_3") (pintype "passive"))
      (node (ref "OUT3") (pin "1") (pinfunction "1_1") (pintype "passive"))
    )
    (net (code "57") (name "Net-(K4-Pad1)") (class "Default")
      (node (ref "K4") (pin "1") (pinfunction "1_1") (pintype "passive"))
      (node (ref "OUT4") (pin "2") (pinfunction "2_2") (pintype "passive"))
    )
    (net (code "58") (name "Net-(K4-Pad3)") (class "Default")
      (node (ref "K4") (pin "3") (pinfunction "3_3") (pintype "passive"))
      (node (ref "OUT4") (pin "1") (pinfunction "1_1") (pintype "passive"))
    )
    (net (code "59") (name "Net-(K5-Pad1)") (class "Default")
      (node (ref "K5") (pin "1") (pinfunction "1_1") (pintype "passive"))
      (node (ref "OUT5") (pin "2") (pinfunction "2_2") (pintype "passive"))
    )
    (net (code "60") (name "Net-(K5-Pad3)") (class "Default")
      (node (ref "K5") (pin "3") (pinfunction "3_3") (pintype "passive"))
      (node (ref "OUT5") (pin "1") (pinfunction "1_1") (pintype "passive"))
    )
    (net (code "61") (name "Net-(K6-Pad1)") (class "Default")
      (node (ref "K6") (pin "1") (pinfunction "1_1") (pintype "passive"))
      (node (ref "OUT6") (pin "2") (pinfunction "2_2") (pintype "passive"))
    )
    (net (code "62") (name "Net-(K6-Pad3)") (class "Default")
      (node (ref "K6") (pin "3") (pinfunction "3_3") (pintype "passive"))
      (node (ref "OUT6") (pin "1") (pinfunction "1_1") (pintype "passive"))
    )
    (net (code "63") (name "Net-(K7-Pad1)") (class "Default")
      (node (ref "K7") (pin "1") (pinfunction "1_1") (pintype "passive"))
      (node (ref "OUT7") (pin "2") (pinfunction "2_2") (pintype "passive"))
    )
    (net (code "64") (name "Net-(K7-Pad3)") (class "Default")
      (node (ref "K7") (pin "3") (pinfunction "3_3") (pintype "passive"))
      (node (ref "OUT7") (pin "1") (pinfunction "1_1") (pintype "passive"))
    )
    (net (code "65") (name "Net-(K8-Pad1)") (class "Default")
      (node (ref "K8") (pin "1") (pinfunction "1_1") (pintype "passive"))
      (node (ref "OUT8") (pin "2") (pinfunction "2_2") (pintype "passive"))
    )
    (net (code "66") (name "Net-(K8-Pad3)") (class "Default")
      (node (ref "K8") (pin "3") (pinfunction "3_3") (pintype "passive"))
      (node (ref "OUT8") (pin "1") (pinfunction "1_1") (pintype "passive"))
    )
    (net (code "67") (name "Net-(KEY1-COMMON1)") (class "Default")
      (node (ref "KEY1") (pin "1") (pinfunction "COMMON1_1") (pintype "passive"))
      (node (ref "Power") (pin "1") (pinfunction "1_1") (pintype "passive"))
    )
    (net (code "68") (name "Net-(KEY1-COMMON2)") (class "Default")
      (node (ref "KEY1") (pin "6") (pinfunction "COMMON2_6") (pintype "passive"))
      (node (ref "Power") (pin "2") (pinfunction "2_2") (pintype "passive"))
    )
    (net (code "69") (name "Net-(LED-A)") (class "Default")
      (node (ref "LED") (pin "1") (pinfunction "A_1") (pintype "passive"))
      (node (ref "R1") (pin "1") (pinfunction "1_1") (pintype "passive"))
    )
    (net (code "70") (name "Net-(PB0-A)") (class "Default")
      (node (ref "PB0") (pin "1") (pinfunction "A_1") (pintype "passive"))
      (node (ref "U8") (pin "2") (pinfunction "K_2") (pintype "passive"))
    )
    (net (code "71") (name "Net-(PB1-A)") (class "Default")
      (node (ref "PB1") (pin "1") (pinfunction "A_1") (pintype "passive"))
      (node (ref "U9") (pin "2") (pinfunction "K_2") (pintype "passive"))
    )
    (net (code "72") (name "Net-(PB2-A)") (class "Default")
      (node (ref "PB2") (pin "1") (pinfunction "A_1") (pintype "passive"))
      (node (ref "U10") (pin "2") (pinfunction "K_2") (pintype "passive"))
    )
    (net (code "73") (name "Net-(PB3-A)") (class "Default")
      (node (ref "PB3") (pin "1") (pinfunction "A_1") (pintype "passive"))
      (node (ref "U11") (pin "2") (pinfunction "K_2") (pintype "passive"))
    )
    (net (code "74") (name "Net-(PC2-A)") (class "Default")
      (node (ref "PC2") (pin "1") (pinfunction "A_1") (pintype "passive"))
      (node (ref "U2") (pin "2") (pinfunction "K_2") (pintype "passive"))
    )
    (net (code "75") (name "Net-(PC3-A)") (class "Default")
      (node (ref "PC3") (pin "1") (pinfunction "A_1") (pintype "passive"))
      (node (ref "U3") (pin "2") (pinfunction "K_2") (pintype "passive"))
    )
    (net (code "76") (name "Net-(PC4-A)") (class "Default")
      (node (ref "PC4") (pin "1") (pinfunction "A_1") (pintype "passive"))
      (node (ref "U5") (pin "2") (pinfunction "K_2") (pintype "passive"))
    )
    (net (code "77") (name "Net-(PC5-A)") (class "Default")
      (node (ref "PC5") (pin "1") (pinfunction "A_1") (pintype "passive"))
      (node (ref "U7") (pin "2") (pinfunction "K_2") (pintype "passive"))
    )
    (net (code "78") (name "Net-(U6-C1+)") (class "Default")
      (node (ref "C5") (pin "1") (pinfunction "1_1") (pintype "passive"))
      (node (ref "U6") (pin "1") (pinfunction "C1+_1") (pintype "passive"))
    )
    (net (code "79") (name "Net-(U6-C1-)") (class "Default")
      (node (ref "C5") (pin "2") (pinfunction "2_2") (pintype "passive"))
      (node (ref "U6") (pin "3") (pinfunction "C1-_3") (pintype "passive"))
    )
    (net (code "80") (name "Net-(U6-C2+)") (class "Default")
      (node (ref "C7") (pin "1") (pinfunction "1_1") (pintype "passive"))
      (node (ref "U6") (pin "4") (pinfunction "C2+_4") (pintype "passive"))
    )
    (net (code "81") (name "Net-(U6-C2-)") (class "Default")
      (node (ref "C7") (pin "2") (pinfunction "2_2") (pintype "passive"))
      (node (ref "U6") (pin "5") (pinfunction "C2-_5") (pintype "passive"))
    )
    (net (code "82") (name "Net-(U6-R1IN)") (class "Default")
      (node (ref "J1") (pin "3") (pinfunction "3_3") (pintype "passive"))
      (node (ref "U6") (pin "13") (pinfunction "R1IN_13") (pintype "passive"))
    )
    (net (code "83") (name "Net-(U6-T1OUT)") (class "Default")
      (node (ref "J1") (pin "2") (pinfunction "2_2") (pintype "passive"))
      (node (ref "U6") (pin "14") (pinfunction "T1OUT_14") (pintype "passive"))
    )
    (net (code "84") (name "Net-(U6-V+)") (class "Default")
      (node (ref "C6") (pin "1") (pinfunction "1_1") (pintype "passive"))
      (node (ref "U6") (pin "2") (pinfunction "V+_2") (pintype "passive"))
    )
    (net (code "85") (name "Net-(U6-V-)") (class "Default")
      (node (ref "C8") (pin "2") (pinfunction "2_2") (pintype "passive"))
      (node (ref "U6") (pin "6") (pinfunction "V-_6") (pintype "passive"))
    )
    (net (code "86") (name "VCC") (class "Default")
      (node (ref "1") (pin "2") (pinfunction "2_2") (pintype "passive"))
      (node (ref "C3") (pin "1") (pinfunction "1_1") (pintype "passive"))
      (node (ref "C4") (pin "2") (pinfunction "2_2") (pintype "passive"))
      (node (ref "C6") (pin "2") (pinfunction "2_2") (pintype "passive"))
      (node (ref "L1") (pin "2") (pinfunction "2_2") (pintype "passive"))
      (node (ref "R1") (pin "2") (pinfunction "2_2") (pintype "passive"))
      (node (ref "R2") (pin "1") (pinfunction "1_1") (pintype "passive"))
      (node (ref "R3") (pin "1") (pinfunction "1_1") (pintype "passive"))
      (node (ref "R4") (pin "2") (pinfunction "2_2") (pintype "passive"))
      (node (ref "U1") (pin "4") (pinfunction "FB_4") (pintype "input"))
      (node (ref "U4") (pin "20") (pinfunction "AVCC_20") (pintype "passive"))
      (node (ref "U4") (pin "21") (pinfunction "AREF_21") (pintype "passive"))
      (node (ref "U4") (pin "7") (pinfunction "VCC_7") (pintype "passive"))
      (node (ref "U6") (pin "16") (pinfunction "VCC_16") (pintype "passive"))
    )
    (net (code "87") (name "unconnected-(1-Pad3)") (class "Default")
      (node (ref "1") (pin "3") (pinfunction "3_3") (pintype "passive"))
    )
    (net (code "88") (name "unconnected-(J1-MH1-Pad10)") (class "Default")
      (node (ref "J1") (pin "10") (pinfunction "MH1_10") (pintype "passive"))
    )
    (net (code "89") (name "unconnected-(J1-MH2-Pad11)") (class "Default")
      (node (ref "J1") (pin "11") (pinfunction "MH2_11") (pintype "passive"))
    )
    (net (code "90") (name "unconnected-(J1-Pad1)") (class "Default")
      (node (ref "J1") (pin "1") (pinfunction "1_1") (pintype "passive"))
    )
    (net (code "91") (name "unconnected-(J1-Pad4)") (class "Default")
      (node (ref "J1") (pin "4") (pinfunction "4_4") (pintype "passive"))
    )
    (net (code "92") (name "unconnected-(J1-Pad6)") (class "Default")
      (node (ref "J1") (pin "6") (pinfunction "6_6") (pintype "passive"))
    )
    (net (code "93") (name "unconnected-(J1-Pad7)") (class "Default")
      (node (ref "J1") (pin "7") (pinfunction "7_7") (pintype "passive"))
    )
    (net (code "94") (name "unconnected-(J1-Pad8)") (class "Default")
      (node (ref "J1") (pin "8") (pinfunction "8_8") (pintype "passive"))
    )
    (net (code "95") (name "unconnected-(J1-Pad9)") (class "Default")
      (node (ref "J1") (pin "9") (pinfunction "9_9") (pintype "passive"))
    )
    (net (code "96") (name "unconnected-(K1-Pad2)") (class "Default")
      (node (ref "K1") (pin "2") (pinfunction "2_2") (pintype "passive"))
    )
    (net (code "97") (name "unconnected-(K2-Pad2)") (class "Default")
      (node (ref "K2") (pin "2") (pinfunction "2_2") (pintype "passive"))
    )
    (net (code "98") (name "unconnected-(K3-Pad2)") (class "Default")
      (node (ref "K3") (pin "2") (pinfunction "2_2") (pintype "passive"))
    )
    (net (code "99") (name "unconnected-(K4-Pad2)") (class "Default")
      (node (ref "K4") (pin "2") (pinfunction "2_2") (pintype "passive"))
    )
    (net (code "100") (name "unconnected-(K5-Pad2)") (class "Default")
      (node (ref "K5") (pin "2") (pinfunction "2_2") (pintype "passive"))
    )
    (net (code "101") (name "unconnected-(K6-Pad2)") (class "Default")
      (node (ref "K6") (pin "2") (pinfunction "2_2") (pintype "passive"))
    )
    (net (code "102") (name "unconnected-(K7-Pad2)") (class "Default")
      (node (ref "K7") (pin "2") (pinfunction "2_2") (pintype "passive"))
    )
    (net (code "103") (name "unconnected-(K8-Pad2)") (class "Default")
      (node (ref "K8") (pin "2") (pinfunction "2_2") (pintype "passive"))
    )
    (net (code "104") (name "unconnected-(U6-R2IN-Pad8)") (class "Default")
      (node (ref "U6") (pin "8") (pinfunction "R2IN_8") (pintype "passive"))
    )
    (net (code "105") (name "unconnected-(U6-R2OUT-Pad9)") (class "Default")
      (node (ref "U6") (pin "9") (pinfunction "R2OUT_9") (pintype "passive"))
    )
    (net (code "106") (name "unconnected-(U6-T2IN-Pad10)") (class "Default")
      (node (ref "U6") (pin "10") (pinfunction "T2IN_10") (pintype "passive"))
    )
    (net (code "107") (name "unconnected-(U6-T2OUT-Pad7)") (class "Default")
      (node (ref "U6") (pin "7") (pinfunction "T2OUT_7") (pintype "passive"))
    )
  )
)
